# KidRobot_V1_1.net
KiCad netlist of a schematic drawn in EAGLE
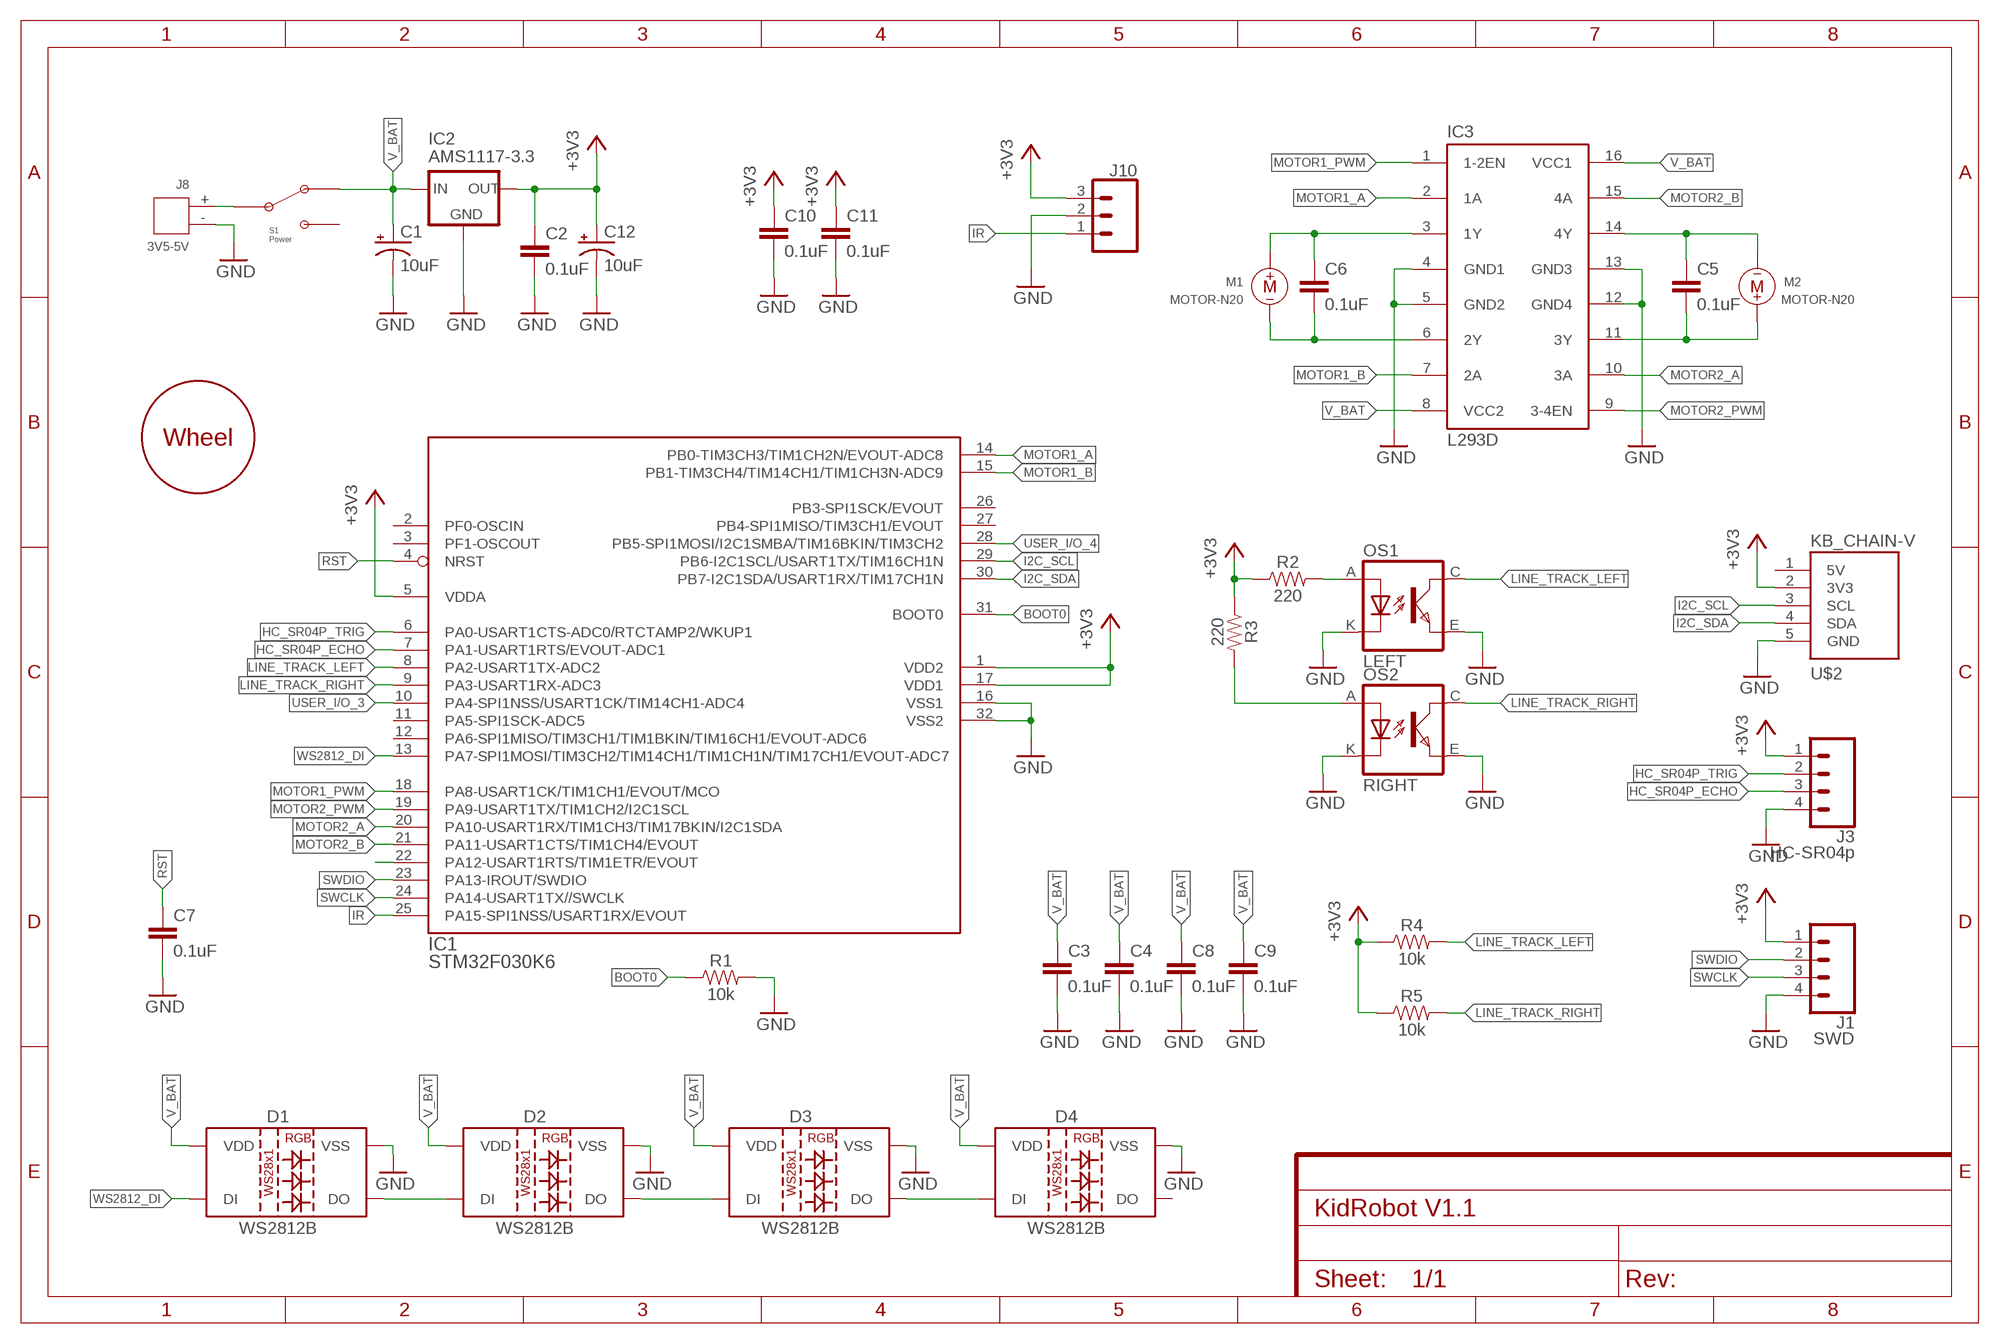
[diagram p0: schematic, sheet 1]

(export (version "E")
  (design (tool "Eeschema 10.0.6"))
  (components
    (comp (ref "C1")
      (value "10uF")
      (footprint "eagle-import:CPOL-RADIAL-2.5MM-5MM")
      (libsource (lib "eagle-import") (part "10UF-POLAR-RADIAL-2.5MM-25V-20%"))
    )
    (comp (ref "C2")
      (value "0.1uF")
      (footprint "eagle-import:0603")
      (libsource (lib "eagle-import") (part "0.1UF-0603-25V-(+80/-20%)"))
    )
    (comp (ref "C3")
      (value "0.1uF")
      (footprint "eagle-import:0603")
      (libsource (lib "eagle-import") (part "0.1UF-0603-25V-(+80/-20%)"))
    )
    (comp (ref "C4")
      (value "0.1uF")
      (footprint "eagle-import:0603")
      (libsource (lib "eagle-import") (part "0.1UF-0603-25V-(+80/-20%)"))
    )
    (comp (ref "C5")
      (value "0.1uF")
      (footprint "eagle-import:0603")
      (libsource (lib "eagle-import") (part "0.1UF-0603-25V-(+80/-20%)"))
    )
    (comp (ref "C6")
      (value "0.1uF")
      (footprint "eagle-import:0603")
      (libsource (lib "eagle-import") (part "0.1UF-0603-25V-(+80/-20%)"))
    )
    (comp (ref "C7")
      (value "0.1uF")
      (footprint "eagle-import:0603")
      (libsource (lib "eagle-import") (part "0.1UF-0603-25V-(+80/-20%)"))
    )
    (comp (ref "C8")
      (value "0.1uF")
      (footprint "eagle-import:0603")
      (libsource (lib "eagle-import") (part "0.1UF-0603-25V-(+80/-20%)"))
    )
    (comp (ref "C9")
      (value "0.1uF")
      (footprint "eagle-import:0603")
      (libsource (lib "eagle-import") (part "0.1UF-0603-25V-(+80/-20%)"))
    )
    (comp (ref "C10")
      (value "0.1uF")
      (footprint "eagle-import:0603")
      (libsource (lib "eagle-import") (part "0.1UF-0603-25V-(+80/-20%)"))
    )
    (comp (ref "C11")
      (value "0.1uF")
      (footprint "eagle-import:0603")
      (libsource (lib "eagle-import") (part "0.1UF-0603-25V-(+80/-20%)"))
    )
    (comp (ref "C12")
      (value "10uF")
      (footprint "eagle-import:CPOL-RADIAL-2.5MM-5MM")
      (libsource (lib "eagle-import") (part "10UF-POLAR-RADIAL-2.5MM-25V-20%"))
    )
    (comp (ref "D1")
      (value "WS2812B")
      (footprint "eagle-import:WS2812B")
      (libsource (lib "eagle-import") (part "WS2812B"))
    )
    (comp (ref "D2")
      (value "WS2812B")
      (footprint "eagle-import:WS2812B")
      (libsource (lib "eagle-import") (part "WS2812B"))
    )
    (comp (ref "D3")
      (value "WS2812B")
      (footprint "eagle-import:WS2812B")
      (libsource (lib "eagle-import") (part "WS2812B"))
    )
    (comp (ref "D4")
      (value "WS2812B")
      (footprint "eagle-import:WS2812B")
      (libsource (lib "eagle-import") (part "WS2812B"))
    )
    (comp (ref "IC1")
      (value "STM32F030K6")
      (footprint "eagle-import:LQFP32")
      (libsource (lib "eagle-import") (part "STM32F030K6"))
    )
    (comp (ref "IC2")
      (value "AMS1117-3.3")
      (footprint "eagle-import:SOT223")
      (libsource (lib "eagle-import") (part "V_REG_LD1117VXXLD1117-SMD"))
    )
    (comp (ref "IC3")
      (value "L293D")
      (footprint "eagle-import:DIL16")
      (libsource (lib "eagle-import") (part "L293D"))
    )
    (comp (ref "J1")
      (value "SWD")
      (footprint "eagle-import:1X04")
      (libsource (lib "eagle-import") (part "CONN_04"))
    )
    (comp (ref "J3")
      (value "HC-SR04p")
      (footprint "eagle-import:1X04")
      (libsource (lib "eagle-import") (part "CONN_04"))
    )
    (comp (ref "J8")
      (value "3V5-5V")
      (footprint "eagle-import:H2-2.0-6X4.5MM")
      (libsource (lib "eagle-import") (part "DIP-JST-2P-2.0"))
    )
    (comp (ref "J10")
      (value "IR Receiver")
      (footprint "eagle-import:1X03")
      (libsource (lib "eagle-import") (part "CONN_03"))
    )
    (comp (ref "M1")
      (value "MOTOR-N20")
      (footprint "eagle-import:MOTOR-GEAR-N20")
      (libsource (lib "eagle-import") (part "MOTOR-N20"))
    )
    (comp (ref "M2")
      (value "MOTOR-N20")
      (footprint "eagle-import:MOTOR-GEAR-N20")
      (libsource (lib "eagle-import") (part "MOTOR-N20"))
    )
    (comp (ref "OS1")
      (value "LEFT")
      (footprint "eagle-import:TCRT5000")
      (libsource (lib "eagle-import") (part "TCRT5000"))
    )
    (comp (ref "OS2")
      (value "RIGHT")
      (footprint "eagle-import:TCRT5000")
      (libsource (lib "eagle-import") (part "TCRT5000"))
    )
    (comp (ref "R1")
      (value "10k")
      (footprint "eagle-import:0603")
      (libsource (lib "eagle-import") (part "10KOHM-0603-1/10W-1%"))
    )
    (comp (ref "R2")
      (value "220")
      (footprint "eagle-import:0603")
      (libsource (lib "eagle-import") (part "220OHM-0603-1/10W-1%"))
    )
    (comp (ref "R3")
      (value "220")
      (footprint "eagle-import:0603")
      (libsource (lib "eagle-import") (part "220OHM-0603-1/10W-1%"))
    )
    (comp (ref "R4")
      (value "10k")
      (footprint "eagle-import:0603")
      (libsource (lib "eagle-import") (part "10KOHM-0603-1/10W-1%"))
    )
    (comp (ref "R5")
      (value "10k")
      (footprint "eagle-import:0603")
      (libsource (lib "eagle-import") (part "10KOHM-0603-1/10W-1%"))
    )
    (comp (ref "S1")
      (value "Power")
      (footprint "eagle-import:SLIDESWITCHES-13X5.5MM")
      (libsource (lib "eagle-import") (part "SLIDESWITCHES-13X5.5MM-VER"))
    )
    (comp (ref "U$1")
      (value "WHEEL")
      (footprint "eagle-import:WHEEL")
      (libsource (lib "eagle-import") (part "WHEEL"))
    )
    (comp (ref "U$2")
      (value "KB_CHAIN-V")
      (footprint "eagle-import:JST5PIN-V")
      (libsource (lib "eagle-import") (part "KB_CHAIN-V"))
    )
  )
  (nets
    (net (code "1") (name "+3V3") (class "Default")
      (node (ref "C10") (pin "1") (pinfunction "1_1") (pintype "passive"))
      (node (ref "C11") (pin "1") (pinfunction "1_1") (pintype "passive"))
      (node (ref "C12") (pin "1") (pinfunction "+_1") (pintype "passive"))
      (node (ref "C2") (pin "1") (pinfunction "1_1") (pintype "passive"))
      (node (ref "IC1") (pin "1") (pinfunction "VDD2_1") (pintype "bidirectional"))
      (node (ref "IC1") (pin "17") (pinfunction "VDD1_17") (pintype "bidirectional"))
      (node (ref "IC1") (pin "5") (pinfunction "VDDA_5") (pintype "bidirectional"))
      (node (ref "IC2") (pin "2") (pinfunction "OUT_2") (pintype "passive"))
      (node (ref "J1") (pin "1") (pinfunction "1_1") (pintype "passive"))
      (node (ref "J10") (pin "3") (pinfunction "3_3") (pintype "passive"))
      (node (ref "J3") (pin "1") (pinfunction "1_1") (pintype "passive"))
      (node (ref "R2") (pin "1") (pinfunction "1_1") (pintype "passive"))
      (node (ref "R3") (pin "1") (pinfunction "1_1") (pintype "passive"))
      (node (ref "R4") (pin "1") (pinfunction "1_1") (pintype "passive"))
      (node (ref "R5") (pin "1") (pinfunction "1_1") (pintype "passive"))
      (node (ref "U$2") (pin "2") (pinfunction "3V3_2") (pintype "bidirectional"))
    )
    (net (code "2") (name "BOOT0") (class "Default")
      (node (ref "IC1") (pin "31") (pinfunction "BOOT0_31") (pintype "input"))
      (node (ref "R1") (pin "1") (pinfunction "1_1") (pintype "passive"))
    )
    (net (code "3") (name "GND") (class "Default")
      (node (ref "C1") (pin "2") (pinfunction "-_2") (pintype "passive"))
      (node (ref "C10") (pin "2") (pinfunction "2_2") (pintype "passive"))
      (node (ref "C11") (pin "2") (pinfunction "2_2") (pintype "passive"))
      (node (ref "C12") (pin "2") (pinfunction "-_2") (pintype "passive"))
      (node (ref "C2") (pin "2") (pinfunction "2_2") (pintype "passive"))
      (node (ref "C3") (pin "2") (pinfunction "2_2") (pintype "passive"))
      (node (ref "C4") (pin "2") (pinfunction "2_2") (pintype "passive"))
      (node (ref "C7") (pin "2") (pinfunction "2_2") (pintype "passive"))
      (node (ref "C8") (pin "2") (pinfunction "2_2") (pintype "passive"))
      (node (ref "C9") (pin "2") (pinfunction "2_2") (pintype "passive"))
      (node (ref "D1") (pin "3") (pinfunction "VSS_3") (pintype "bidirectional"))
      (node (ref "D2") (pin "3") (pinfunction "VSS_3") (pintype "bidirectional"))
      (node (ref "D3") (pin "3") (pinfunction "VSS_3") (pintype "bidirectional"))
      (node (ref "D4") (pin "3") (pinfunction "VSS_3") (pintype "bidirectional"))
      (node (ref "IC1") (pin "16") (pinfunction "VSS1_16") (pintype "bidirectional"))
      (node (ref "IC1") (pin "32") (pinfunction "VSS2_32") (pintype "bidirectional"))
      (node (ref "IC2") (pin "1") (pinfunction "GND_1") (pintype "input"))
      (node (ref "IC3") (pin "12") (pinfunction "GND4_12") (pintype "power_in"))
      (node (ref "IC3") (pin "13") (pinfunction "GND3_13") (pintype "power_in"))
      (node (ref "IC3") (pin "4") (pinfunction "GND1_4") (pintype "power_in"))
      (node (ref "IC3") (pin "5") (pinfunction "GND2_5") (pintype "power_in"))
      (node (ref "J1") (pin "4") (pinfunction "4_4") (pintype "passive"))
      (node (ref "J10") (pin "2") (pinfunction "2_2") (pintype "passive"))
      (node (ref "J3") (pin "4") (pinfunction "4_4") (pintype "passive"))
      (node (ref "J8") (pin "-") (pinfunction "P$2_-") (pintype "bidirectional"))
      (node (ref "OS1") (pin "E") (pinfunction "EMITTER_E") (pintype "passive"))
      (node (ref "OS1") (pin "K") (pinfunction "CATHODE_K") (pintype "passive"))
      (node (ref "OS2") (pin "E") (pinfunction "EMITTER_E") (pintype "passive"))
      (node (ref "OS2") (pin "K") (pinfunction "CATHODE_K") (pintype "passive"))
      (node (ref "R1") (pin "2") (pinfunction "2_2") (pintype "passive"))
      (node (ref "U$2") (pin "5") (pinfunction "GND_5") (pintype "bidirectional"))
    )
    (net (code "4") (name "HC_SR04P_ECHO") (class "Default")
      (node (ref "IC1") (pin "7") (pinfunction "PA1-USART1RTS/EVOUT-ADC1_7") (pintype "bidirectional"))
      (node (ref "J3") (pin "3") (pinfunction "3_3") (pintype "passive"))
    )
    (net (code "5") (name "HC_SR04P_TRIG") (class "Default")
      (node (ref "IC1") (pin "6") (pinfunction "PA0-USART1CTS-ADC0/RTCTAMP2/WKUP1_6") (pintype "bidirectional"))
      (node (ref "J3") (pin "2") (pinfunction "2_2") (pintype "passive"))
    )
    (net (code "6") (name "I2C_SCL") (class "Default")
      (node (ref "IC1") (pin "29") (pinfunction "PB6-I2C1SCL/USART1TX/TIM16CH1N_29") (pintype "bidirectional"))
      (node (ref "U$2") (pin "3") (pinfunction "SCL_3") (pintype "bidirectional"))
    )
    (net (code "7") (name "I2C_SDA") (class "Default")
      (node (ref "IC1") (pin "30") (pinfunction "PB7-I2C1SDA/USART1RX/TIM17CH1N_30") (pintype "bidirectional"))
      (node (ref "U$2") (pin "4") (pinfunction "SDA_4") (pintype "bidirectional"))
    )
    (net (code "8") (name "IR") (class "Default")
      (node (ref "IC1") (pin "25") (pinfunction "PA15-SPI1NSS/USART1RX/EVOUT_25") (pintype "bidirectional"))
      (node (ref "J10") (pin "1") (pinfunction "1_1") (pintype "passive"))
    )
    (net (code "9") (name "LINE_TRACK_LEFT") (class "Default")
      (node (ref "IC1") (pin "8") (pinfunction "PA2-USART1TX-ADC2_8") (pintype "bidirectional"))
      (node (ref "OS1") (pin "C") (pinfunction "COLLECTOR_C") (pintype "passive"))
      (node (ref "R4") (pin "2") (pinfunction "2_2") (pintype "passive"))
    )
    (net (code "10") (name "LINE_TRACK_RIGHT") (class "Default")
      (node (ref "IC1") (pin "9") (pinfunction "PA3-USART1RX-ADC3_9") (pintype "bidirectional"))
      (node (ref "OS2") (pin "C") (pinfunction "COLLECTOR_C") (pintype "passive"))
      (node (ref "R5") (pin "2") (pinfunction "2_2") (pintype "passive"))
    )
    (net (code "11") (name "MOTOR1_A") (class "Default")
      (node (ref "IC1") (pin "14") (pinfunction "PB0-TIM3CH3/TIM1CH2N/EVOUT-ADC8_14") (pintype "bidirectional"))
      (node (ref "IC3") (pin "2") (pinfunction "1A_2") (pintype "input"))
    )
    (net (code "12") (name "MOTOR1_B") (class "Default")
      (node (ref "IC1") (pin "15") (pinfunction "PB1-TIM3CH4/TIM14CH1/TIM1CH3N-ADC9_15") (pintype "bidirectional"))
      (node (ref "IC3") (pin "7") (pinfunction "2A_7") (pintype "input"))
    )
    (net (code "13") (name "MOTOR1_PWM") (class "Default")
      (node (ref "IC1") (pin "18") (pinfunction "PA8-USART1CK/TIM1CH1/EVOUT/MCO_18") (pintype "bidirectional"))
      (node (ref "IC3") (pin "1") (pinfunction "1-2EN_1") (pintype "input"))
    )
    (net (code "14") (name "MOTOR2_A") (class "Default")
      (node (ref "IC1") (pin "20") (pinfunction "PA10-USART1RX/TIM1CH3/TIM17BKIN/I2C1SDA_20") (pintype "bidirectional"))
      (node (ref "IC3") (pin "10") (pinfunction "3A_10") (pintype "input"))
    )
    (net (code "15") (name "MOTOR2_B") (class "Default")
      (node (ref "IC1") (pin "21") (pinfunction "PA11-USART1CTS/TIM1CH4/EVOUT_21") (pintype "bidirectional"))
      (node (ref "IC3") (pin "15") (pinfunction "4A_15") (pintype "input"))
    )
    (net (code "16") (name "MOTOR2_PWM") (class "Default")
      (node (ref "IC1") (pin "19") (pinfunction "PA9-USART1TX/TIM1CH2/I2C1SCL_19") (pintype "bidirectional"))
      (node (ref "IC3") (pin "9") (pinfunction "3-4EN_9") (pintype "input"))
    )
    (net (code "17") (name "Net-(D1-DO)") (class "Default")
      (node (ref "D1") (pin "2") (pinfunction "DO_2") (pintype "bidirectional"))
      (node (ref "D2") (pin "4") (pinfunction "DI_4") (pintype "bidirectional"))
    )
    (net (code "18") (name "Net-(D2-DO)") (class "Default")
      (node (ref "D2") (pin "2") (pinfunction "DO_2") (pintype "bidirectional"))
      (node (ref "D3") (pin "4") (pinfunction "DI_4") (pintype "bidirectional"))
    )
    (net (code "19") (name "Net-(D3-DO)") (class "Default")
      (node (ref "D3") (pin "2") (pinfunction "DO_2") (pintype "bidirectional"))
      (node (ref "D4") (pin "4") (pinfunction "DI_4") (pintype "bidirectional"))
    )
    (net (code "20") (name "Net-(IC3-1Y)") (class "Default")
      (node (ref "C6") (pin "1") (pinfunction "1_1") (pintype "passive"))
      (node (ref "IC3") (pin "3") (pinfunction "1Y_3") (pintype "output"))
      (node (ref "M1") (pin "+") (pinfunction "+_+") (pintype "bidirectional"))
    )
    (net (code "21") (name "Net-(IC3-2Y)") (class "Default")
      (node (ref "C6") (pin "2") (pinfunction "2_2") (pintype "passive"))
      (node (ref "IC3") (pin "6") (pinfunction "2Y_6") (pintype "output"))
      (node (ref "M1") (pin "-") (pinfunction "-_-") (pintype "bidirectional"))
    )
    (net (code "22") (name "Net-(IC3-3Y)") (class "Default")
      (node (ref "C5") (pin "2") (pinfunction "2_2") (pintype "passive"))
      (node (ref "IC3") (pin "11") (pinfunction "3Y_11") (pintype "output"))
      (node (ref "M2") (pin "+") (pinfunction "+_+") (pintype "bidirectional"))
    )
    (net (code "23") (name "Net-(IC3-4Y)") (class "Default")
      (node (ref "C5") (pin "1") (pinfunction "1_1") (pintype "passive"))
      (node (ref "IC3") (pin "14") (pinfunction "4Y_14") (pintype "output"))
      (node (ref "M2") (pin "-") (pinfunction "-_-") (pintype "bidirectional"))
    )
    (net (code "24") (name "Net-(J8-P$1)") (class "Default")
      (node (ref "J8") (pin "+") (pinfunction "P$1_+") (pintype "bidirectional"))
      (node (ref "S1") (pin "2") (pinfunction "2_2") (pintype "bidirectional"))
    )
    (net (code "25") (name "Net-(OS1-ANODE)") (class "Default")
      (node (ref "OS1") (pin "A") (pinfunction "ANODE_A") (pintype "passive"))
      (node (ref "R2") (pin "2") (pinfunction "2_2") (pintype "passive"))
    )
    (net (code "26") (name "Net-(OS2-ANODE)") (class "Default")
      (node (ref "OS2") (pin "A") (pinfunction "ANODE_A") (pintype "passive"))
      (node (ref "R3") (pin "2") (pinfunction "2_2") (pintype "passive"))
    )
    (net (code "27") (name "RST") (class "Default")
      (node (ref "C7") (pin "1") (pinfunction "1_1") (pintype "passive"))
      (node (ref "IC1") (pin "4") (pinfunction "NRST_4") (pintype "bidirectional"))
    )
    (net (code "28") (name "SWCLK") (class "Default")
      (node (ref "IC1") (pin "24") (pinfunction "PA14-USART1TX//SWCLK_24") (pintype "bidirectional"))
      (node (ref "J1") (pin "3") (pinfunction "3_3") (pintype "passive"))
    )
    (net (code "29") (name "SWDIO") (class "Default")
      (node (ref "IC1") (pin "23") (pinfunction "PA13-IROUT/SWDIO_23") (pintype "bidirectional"))
      (node (ref "J1") (pin "2") (pinfunction "2_2") (pintype "passive"))
    )
    (net (code "30") (name "USER_I{slash}O_3") (class "Default")
      (node (ref "IC1") (pin "10") (pinfunction "PA4-SPI1NSS/USART1CK/TIM14CH1-ADC4_10") (pintype "bidirectional"))
    )
    (net (code "31") (name "USER_I{slash}O_4") (class "Default")
      (node (ref "IC1") (pin "28") (pinfunction "PB5-SPI1MOSI/I2C1SMBA/TIM16BKIN/TIM3CH2_28") (pintype "bidirectional"))
    )
    (net (code "32") (name "V_BAT") (class "Default")
      (node (ref "C1") (pin "1") (pinfunction "+_1") (pintype "passive"))
      (node (ref "C3") (pin "1") (pinfunction "1_1") (pintype "passive"))
      (node (ref "C4") (pin "1") (pinfunction "1_1") (pintype "passive"))
      (node (ref "C8") (pin "1") (pinfunction "1_1") (pintype "passive"))
      (node (ref "C9") (pin "1") (pinfunction "1_1") (pintype "passive"))
      (node (ref "D1") (pin "1") (pinfunction "VDD_1") (pintype "bidirectional"))
      (node (ref "D2") (pin "1") (pinfunction "VDD_1") (pintype "bidirectional"))
      (node (ref "D3") (pin "1") (pinfunction "VDD_1") (pintype "bidirectional"))
      (node (ref "D4") (pin "1") (pinfunction "VDD_1") (pintype "bidirectional"))
      (node (ref "IC2") (pin "3") (pinfunction "IN_3") (pintype "input"))
      (node (ref "IC3") (pin "16") (pinfunction "VCC1_16") (pintype "power_in"))
      (node (ref "IC3") (pin "8") (pinfunction "VCC2_8") (pintype "power_in"))
      (node (ref "S1") (pin "1") (pinfunction "1_1") (pintype "bidirectional"))
    )
    (net (code "33") (name "WS2812_DI") (class "Default")
      (node (ref "D1") (pin "4") (pinfunction "DI_4") (pintype "bidirectional"))
      (node (ref "IC1") (pin "13") (pinfunction "PA7-SPI1MOSI/TIM3CH2/TIM14CH1/TIM1CH1N/TIM17CH1/EVOUT-ADC7_13") (pintype "bidirectional"))
    )
    (net (code "34") (name "unconnected-(D4-DO-Pad2)") (class "Default")
      (node (ref "D4") (pin "2") (pinfunction "DO_2") (pintype "bidirectional"))
    )
    (net (code "35") (name "unconnected-(IC1-PA5-SPI1SCK-ADC5-Pad11)") (class "Default")
      (node (ref "IC1") (pin "11") (pinfunction "PA5-SPI1SCK-ADC5_11") (pintype "bidirectional"))
    )
    (net (code "36") (name "unconnected-(IC1-PA6-SPI1MISO{slash}TIM3CH1{slash}TIM1BKIN{slash}TIM16CH1{slash}EVOUT-ADC6-Pad12)") (class "Default")
      (node (ref "IC1") (pin "12") (pinfunction "PA6-SPI1MISO/TIM3CH1/TIM1BKIN/TIM16CH1/EVOUT-ADC6_12") (pintype "bidirectional"))
    )
    (net (code "37") (name "unconnected-(IC1-PA12-USART1RTS{slash}TIM1ETR{slash}EVOUT-Pad22)") (class "Default")
      (node (ref "IC1") (pin "22") (pinfunction "PA12-USART1RTS/TIM1ETR/EVOUT_22") (pintype "bidirectional"))
    )
    (net (code "38") (name "unconnected-(IC1-PB3-SPI1SCK{slash}EVOUT-Pad26)") (class "Default")
      (node (ref "IC1") (pin "26") (pinfunction "PB3-SPI1SCK/EVOUT_26") (pintype "bidirectional"))
    )
    (net (code "39") (name "unconnected-(IC1-PB4-SPI1MISO{slash}TIM3CH1{slash}EVOUT-Pad27)") (class "Default")
      (node (ref "IC1") (pin "27") (pinfunction "PB4-SPI1MISO/TIM3CH1/EVOUT_27") (pintype "bidirectional"))
    )
    (net (code "40") (name "unconnected-(IC1-PF0-OSCIN-Pad2)") (class "Default")
      (node (ref "IC1") (pin "2") (pinfunction "PF0-OSCIN_2") (pintype "bidirectional"))
    )
    (net (code "41") (name "unconnected-(IC1-PF1-OSCOUT-Pad3)") (class "Default")
      (node (ref "IC1") (pin "3") (pinfunction "PF1-OSCOUT_3") (pintype "bidirectional"))
    )
    (net (code "42") (name "unconnected-(S1-Pad3)") (class "Default")
      (node (ref "S1") (pin "3") (pinfunction "3_3") (pintype "bidirectional"))
    )
    (net (code "43") (name "unconnected-(U$2-5V-Pad1)") (class "Default")
      (node (ref "U$2") (pin "1") (pinfunction "5V_1") (pintype "bidirectional"))
    )
  )
)
